# alswitch.net
KiCad netlist of a schematic drawn in EAGLE
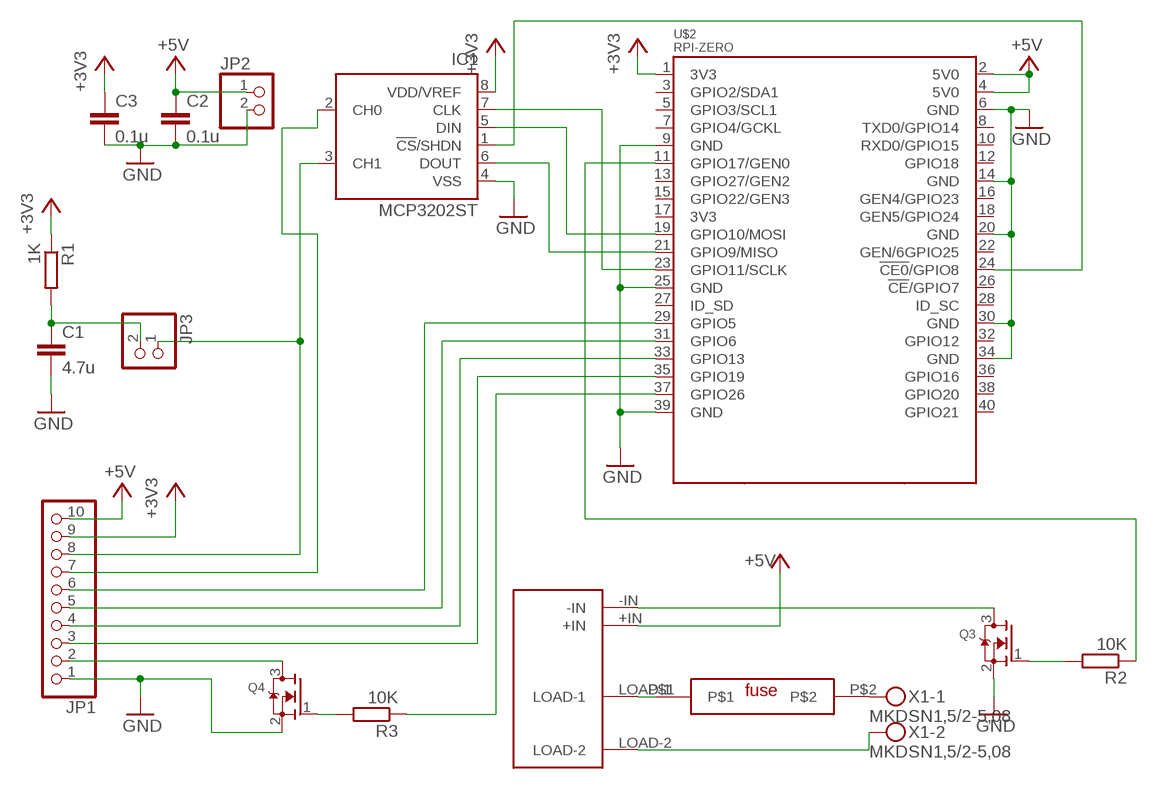
[diagram p0: schematic, sheet 1]

(export (version "E")
  (design (tool "Eeschema 10.0.6"))
  (components
    (comp (ref "C1")
      (value "4.7u")
      (footprint "eagle-import:C1206")
      (libsource (lib "eagle-import") (part "C-EUC1206"))
    )
    (comp (ref "C2")
      (value "0.1u")
      (footprint "eagle-import:C1206")
      (libsource (lib "eagle-import") (part "C-EUC1206"))
    )
    (comp (ref "C3")
      (value "0.1u")
      (footprint "eagle-import:C1206")
      (libsource (lib "eagle-import") (part "C-EUC1206"))
    )
    (comp (ref "IC1")
      (value "MCP3202ST")
      (footprint "eagle-import:TSSOP8")
      (fields (field (name "MF") "MICROCHIP") (field (name "MPN") "MCP3202-CI/ST"))
      (libsource (lib "eagle-import") (part "MCP3202ST"))
    )
    (comp (ref "JP1")
      (value "PINHD-1X10")
      (footprint "eagle-import:1X10")
      (libsource (lib "eagle-import") (part "PINHD-1X10"))
    )
    (comp (ref "JP2")
      (value "PINHD-1X2")
      (footprint "eagle-import:1X02")
      (libsource (lib "eagle-import") (part "PINHD-1X2"))
    )
    (comp (ref "JP3")
      (value "PINHD-1X2")
      (footprint "eagle-import:1X02")
      (libsource (lib "eagle-import") (part "PINHD-1X2"))
    )
    (comp (ref "Q3")
      (value "MOSFET-NREFLOW")
      (footprint "eagle-import:SOT23")
      (libsource (lib "eagle-import") (part "MOSFET-NREFLOW"))
    )
    (comp (ref "Q4")
      (value "MOSFET-NREFLOW")
      (footprint "eagle-import:SOT23")
      (libsource (lib "eagle-import") (part "MOSFET-NREFLOW"))
    )
    (comp (ref "R1")
      (value "1K")
      (footprint "eagle-import:R0805")
      (libsource (lib "eagle-import") (part "R-EU_R0805"))
    )
    (comp (ref "R2")
      (value "10K")
      (footprint "eagle-import:R0805")
      (libsource (lib "eagle-import") (part "R-EU_R0805"))
    )
    (comp (ref "R3")
      (value "10K")
      (footprint "eagle-import:R0805")
      (libsource (lib "eagle-import") (part "R-EU_R0805"))
    )
    (comp (ref "U$1")
      (value "FUSE")
      (footprint "eagle-import:FUSE")
      (libsource (lib "eagle-import") (part "FUSE"))
    )
    (comp (ref "U$2")
      (value "RPI-ZERO")
      (footprint "eagle-import:RASPBERRYPI_BASTELSTUBE_V13_RASPI_BOARD_B+_FULL")
      (libsource (lib "eagle-import") (part "RPI-ZERO"))
    )
    (comp (ref "U$3")
      (value "G3MC-201PL")
      (footprint "eagle-import:G3MC-201PL")
      (libsource (lib "eagle-import") (part "G3MC-201PL"))
    )
    (comp (ref "X1")
      (value "MKDSN1,5/2-5,08")
      (footprint "eagle-import:MKDSN1,5_2-5,08")
      (libsource (lib "eagle-import") (part "MKDSN1,5/2-5,08"))
    )
  )
  (nets
    (net (code "1") (name "+3V3") (class "Default")
      (node (ref "C3") (pin "1") (pinfunction "1_1") (pintype "passive"))
      (node (ref "IC1") (pin "8") (pinfunction "VDD/VREF_8") (pintype "input"))
      (node (ref "JP1") (pin "9") (pinfunction "9_9") (pintype "passive"))
      (node (ref "R1") (pin "1") (pinfunction "1_1") (pintype "passive"))
      (node (ref "U$2") (pin "1") (pinfunction "3V3_1") (pintype "power_in"))
    )
    (net (code "2") (name "+5V") (class "Default")
      (node (ref "C2") (pin "1") (pinfunction "1_1") (pintype "passive"))
      (node (ref "JP1") (pin "10") (pinfunction "10_10") (pintype "passive"))
      (node (ref "JP2") (pin "1") (pinfunction "1_1") (pintype "passive"))
      (node (ref "U$2") (pin "2") (pinfunction "5V0_2") (pintype "power_in"))
      (node (ref "U$2") (pin "4") (pinfunction "5V0_4") (pintype "power_in"))
      (node (ref "U$3") (pin "+IN") (pinfunction "+IN_+IN") (pintype "input"))
    )
    (net (code "3") (name "/3V3") (class "Default")
      (node (ref "U$2") (pin "17") (pinfunction "3V3_17") (pintype "power_in"))
    )
    (net (code "4") (name "GND") (class "Default")
      (node (ref "C1") (pin "2") (pinfunction "2_2") (pintype "passive"))
      (node (ref "C2") (pin "2") (pinfunction "2_2") (pintype "passive"))
      (node (ref "C3") (pin "2") (pinfunction "2_2") (pintype "passive"))
      (node (ref "IC1") (pin "4") (pinfunction "VSS_4") (pintype "input"))
      (node (ref "JP1") (pin "1") (pinfunction "1_1") (pintype "passive"))
      (node (ref "JP2") (pin "2") (pinfunction "2_2") (pintype "passive"))
      (node (ref "Q3") (pin "2") (pinfunction "S_2") (pintype "bidirectional"))
      (node (ref "Q4") (pin "2") (pinfunction "S_2") (pintype "bidirectional"))
      (node (ref "U$2") (pin "14") (pinfunction "GND_14") (pintype "power_in"))
      (node (ref "U$2") (pin "20") (pinfunction "GND_20") (pintype "power_in"))
      (node (ref "U$2") (pin "25") (pinfunction "GND_25") (pintype "power_in"))
      (node (ref "U$2") (pin "30") (pinfunction "GND_30") (pintype "power_in"))
      (node (ref "U$2") (pin "34") (pinfunction "GND_34") (pintype "power_in"))
      (node (ref "U$2") (pin "39") (pinfunction "GND_39") (pintype "power_in"))
      (node (ref "U$2") (pin "6") (pinfunction "GND_6") (pintype "power_in"))
      (node (ref "U$2") (pin "9") (pinfunction "GND_9") (pintype "power_in"))
    )
    (net (code "5") (name "Net-(C1-Pad1)") (class "Default")
      (node (ref "C1") (pin "1") (pinfunction "1_1") (pintype "passive"))
      (node (ref "JP3") (pin "2") (pinfunction "2_2") (pintype "passive"))
      (node (ref "R1") (pin "2") (pinfunction "2_2") (pintype "passive"))
    )
    (net (code "6") (name "Net-(IC1-CH0)") (class "Default")
      (node (ref "IC1") (pin "2") (pinfunction "CH0_2") (pintype "input"))
      (node (ref "JP1") (pin "7") (pinfunction "7_7") (pintype "passive"))
    )
    (net (code "7") (name "Net-(IC1-CH1)") (class "Default")
      (node (ref "IC1") (pin "3") (pinfunction "CH1_3") (pintype "input"))
      (node (ref "JP1") (pin "8") (pinfunction "8_8") (pintype "passive"))
      (node (ref "JP3") (pin "1") (pinfunction "1_1") (pintype "passive"))
    )
    (net (code "8") (name "Net-(IC1-CLK)") (class "Default")
      (node (ref "IC1") (pin "7") (pinfunction "CLK_7") (pintype "input"))
      (node (ref "U$2") (pin "23") (pinfunction "GPIO11/SCLK_23") (pintype "bidirectional"))
    )
    (net (code "9") (name "Net-(IC1-DIN)") (class "Default")
      (node (ref "IC1") (pin "5") (pinfunction "DIN_5") (pintype "input"))
      (node (ref "U$2") (pin "19") (pinfunction "GPIO10/MOSI_19") (pintype "bidirectional"))
    )
    (net (code "10") (name "Net-(IC1-DOUT)") (class "Default")
      (node (ref "IC1") (pin "6") (pinfunction "DOUT_6") (pintype "input"))
      (node (ref "U$2") (pin "21") (pinfunction "GPIO9/MISO_21") (pintype "bidirectional"))
    )
    (net (code "11") (name "Net-(IC1-~{CS}{slash}SHDN)") (class "Default")
      (node (ref "IC1") (pin "1") (pinfunction "~{CS}/SHDN_1") (pintype "input"))
      (node (ref "U$2") (pin "24") (pinfunction "~{CE0}/GPIO8_24") (pintype "bidirectional"))
    )
    (net (code "12") (name "Net-(Q3-D)") (class "Default")
      (node (ref "Q3") (pin "3") (pinfunction "D_3") (pintype "bidirectional"))
      (node (ref "U$3") (pin "-IN") (pinfunction "-IN_-IN") (pintype "input"))
    )
    (net (code "13") (name "Net-(Q3-G)") (class "Default")
      (node (ref "Q3") (pin "1") (pinfunction "G_1") (pintype "bidirectional"))
      (node (ref "R2") (pin "2") (pinfunction "2_2") (pintype "passive"))
    )
    (net (code "14") (name "Net-(Q4-D)") (class "Default")
      (node (ref "JP1") (pin "2") (pinfunction "2_2") (pintype "passive"))
      (node (ref "Q4") (pin "3") (pinfunction "D_3") (pintype "bidirectional"))
    )
    (net (code "15") (name "Net-(Q4-G)") (class "Default")
      (node (ref "Q4") (pin "1") (pinfunction "G_1") (pintype "bidirectional"))
      (node (ref "R3") (pin "2") (pinfunction "2_2") (pintype "passive"))
    )
    (net (code "16") (name "Net-(U$1-PadP$1)") (class "Default")
      (node (ref "U$1") (pin "P$1") (pinfunction "P$1_P$1") (pintype "bidirectional"))
      (node (ref "U$3") (pin "LOAD-1") (pinfunction "LOAD-1_LOAD-1") (pintype "bidirectional"))
    )
    (net (code "17") (name "Net-(U$2-GPIO5)") (class "Default")
      (node (ref "JP1") (pin "6") (pinfunction "6_6") (pintype "passive"))
      (node (ref "U$2") (pin "29") (pinfunction "GPIO5_29") (pintype "bidirectional"))
    )
    (net (code "18") (name "Net-(U$2-GPIO6)") (class "Default")
      (node (ref "JP1") (pin "5") (pinfunction "5_5") (pintype "passive"))
      (node (ref "U$2") (pin "31") (pinfunction "GPIO6_31") (pintype "bidirectional"))
    )
    (net (code "19") (name "Net-(U$2-GPIO13)") (class "Default")
      (node (ref "JP1") (pin "4") (pinfunction "4_4") (pintype "passive"))
      (node (ref "U$2") (pin "33") (pinfunction "GPIO13_33") (pintype "bidirectional"))
    )
    (net (code "20") (name "Net-(U$2-GPIO17{slash}GEN0)") (class "Default")
      (node (ref "R2") (pin "1") (pinfunction "1_1") (pintype "passive"))
      (node (ref "U$2") (pin "11") (pinfunction "GPIO17/GEN0_11") (pintype "bidirectional"))
    )
    (net (code "21") (name "Net-(U$2-GPIO19)") (class "Default")
      (node (ref "JP1") (pin "3") (pinfunction "3_3") (pintype "passive"))
      (node (ref "U$2") (pin "35") (pinfunction "GPIO19_35") (pintype "bidirectional"))
    )
    (net (code "22") (name "Net-(U$2-GPIO26)") (class "Default")
      (node (ref "R3") (pin "1") (pinfunction "1_1") (pintype "passive"))
      (node (ref "U$2") (pin "37") (pinfunction "GPIO26_37") (pintype "bidirectional"))
    )
    (net (code "23") (name "Net-(X1A-KL)") (class "Default")
      (node (ref "U$1") (pin "P$2") (pinfunction "P$2_P$2") (pintype "bidirectional"))
      (node (ref "X1") (pin "1") (pinfunction "KL_1") (pintype "passive"))
    )
    (net (code "24") (name "Net-(X1B-KL)") (class "Default")
      (node (ref "U$3") (pin "LOAD-2") (pinfunction "LOAD-2_LOAD-2") (pintype "bidirectional"))
      (node (ref "X1") (pin "2") (pinfunction "KL_2") (pintype "passive"))
    )
    (net (code "25") (name "unconnected-(U$2-GEN4{slash}GPIO23-Pad16)") (class "Default")
      (node (ref "U$2") (pin "16") (pinfunction "GEN4/GPIO23_16") (pintype "bidirectional"))
    )
    (net (code "26") (name "unconnected-(U$2-GEN5{slash}GPIO24-Pad18)") (class "Default")
      (node (ref "U$2") (pin "18") (pinfunction "GEN5/GPIO24_18") (pintype "bidirectional"))
    )
    (net (code "27") (name "unconnected-(U$2-GEN{slash}6GPIO25-Pad22)") (class "Default")
      (node (ref "U$2") (pin "22") (pinfunction "GEN/6GPIO25_22") (pintype "bidirectional"))
    )
    (net (code "28") (name "unconnected-(U$2-GPIO2{slash}SDA1-Pad3)") (class "Default")
      (node (ref "U$2") (pin "3") (pinfunction "GPIO2/SDA1_3") (pintype "bidirectional"))
    )
    (net (code "29") (name "unconnected-(U$2-GPIO3{slash}SCL1-Pad5)") (class "Default")
      (node (ref "U$2") (pin "5") (pinfunction "GPIO3/SCL1_5") (pintype "bidirectional"))
    )
    (net (code "30") (name "unconnected-(U$2-GPIO4{slash}GCKL-Pad7)") (class "Default")
      (node (ref "U$2") (pin "7") (pinfunction "GPIO4/GCKL_7") (pintype "bidirectional"))
    )
    (net (code "31") (name "unconnected-(U$2-GPIO12-Pad32)") (class "Default")
      (node (ref "U$2") (pin "32") (pinfunction "GPIO12_32") (pintype "bidirectional"))
    )
    (net (code "32") (name "unconnected-(U$2-GPIO16-Pad36)") (class "Default")
      (node (ref "U$2") (pin "36") (pinfunction "GPIO16_36") (pintype "bidirectional"))
    )
    (net (code "33") (name "unconnected-(U$2-GPIO18-Pad12)") (class "Default")
      (node (ref "U$2") (pin "12") (pinfunction "GPIO18_12") (pintype "bidirectional"))
    )
    (net (code "34") (name "unconnected-(U$2-GPIO20-Pad38)") (class "Default")
      (node (ref "U$2") (pin "38") (pinfunction "GPIO20_38") (pintype "bidirectional"))
    )
    (net (code "35") (name "unconnected-(U$2-GPIO21-Pad40)") (class "Default")
      (node (ref "U$2") (pin "40") (pinfunction "GPIO21_40") (pintype "bidirectional"))
    )
    (net (code "36") (name "unconnected-(U$2-GPIO22{slash}GEN3-Pad15)") (class "Default")
      (node (ref "U$2") (pin "15") (pinfunction "GPIO22/GEN3_15") (pintype "bidirectional"))
    )
    (net (code "37") (name "unconnected-(U$2-GPIO27{slash}GEN2-Pad13)") (class "Default")
      (node (ref "U$2") (pin "13") (pinfunction "GPIO27/GEN2_13") (pintype "bidirectional"))
    )
    (net (code "38") (name "unconnected-(U$2-ID_SC-Pad28)") (class "Default")
      (node (ref "U$2") (pin "28") (pinfunction "ID_SC_28") (pintype "bidirectional"))
    )
    (net (code "39") (name "unconnected-(U$2-ID_SD-Pad27)") (class "Default")
      (node (ref "U$2") (pin "27") (pinfunction "ID_SD_27") (pintype "bidirectional"))
    )
    (net (code "40") (name "unconnected-(U$2-RXD0{slash}GPIO15-Pad10)") (class "Default")
      (node (ref "U$2") (pin "10") (pinfunction "RXD0/GPIO15_10") (pintype "bidirectional"))
    )
    (net (code "41") (name "unconnected-(U$2-TXD0{slash}GPIO14-Pad8)") (class "Default")
      (node (ref "U$2") (pin "8") (pinfunction "TXD0/GPIO14_8") (pintype "bidirectional"))
    )
    (net (code "42") (name "unconnected-(U$2-~{CE}{slash}GPIO7-Pad26)") (class "Default")
      (node (ref "U$2") (pin "26") (pinfunction "~{CE}/GPIO7_26") (pintype "bidirectional"))
    )
  )
)
